# tinyusbboard.net
KiCad netlist of a schematic drawn in EAGLE
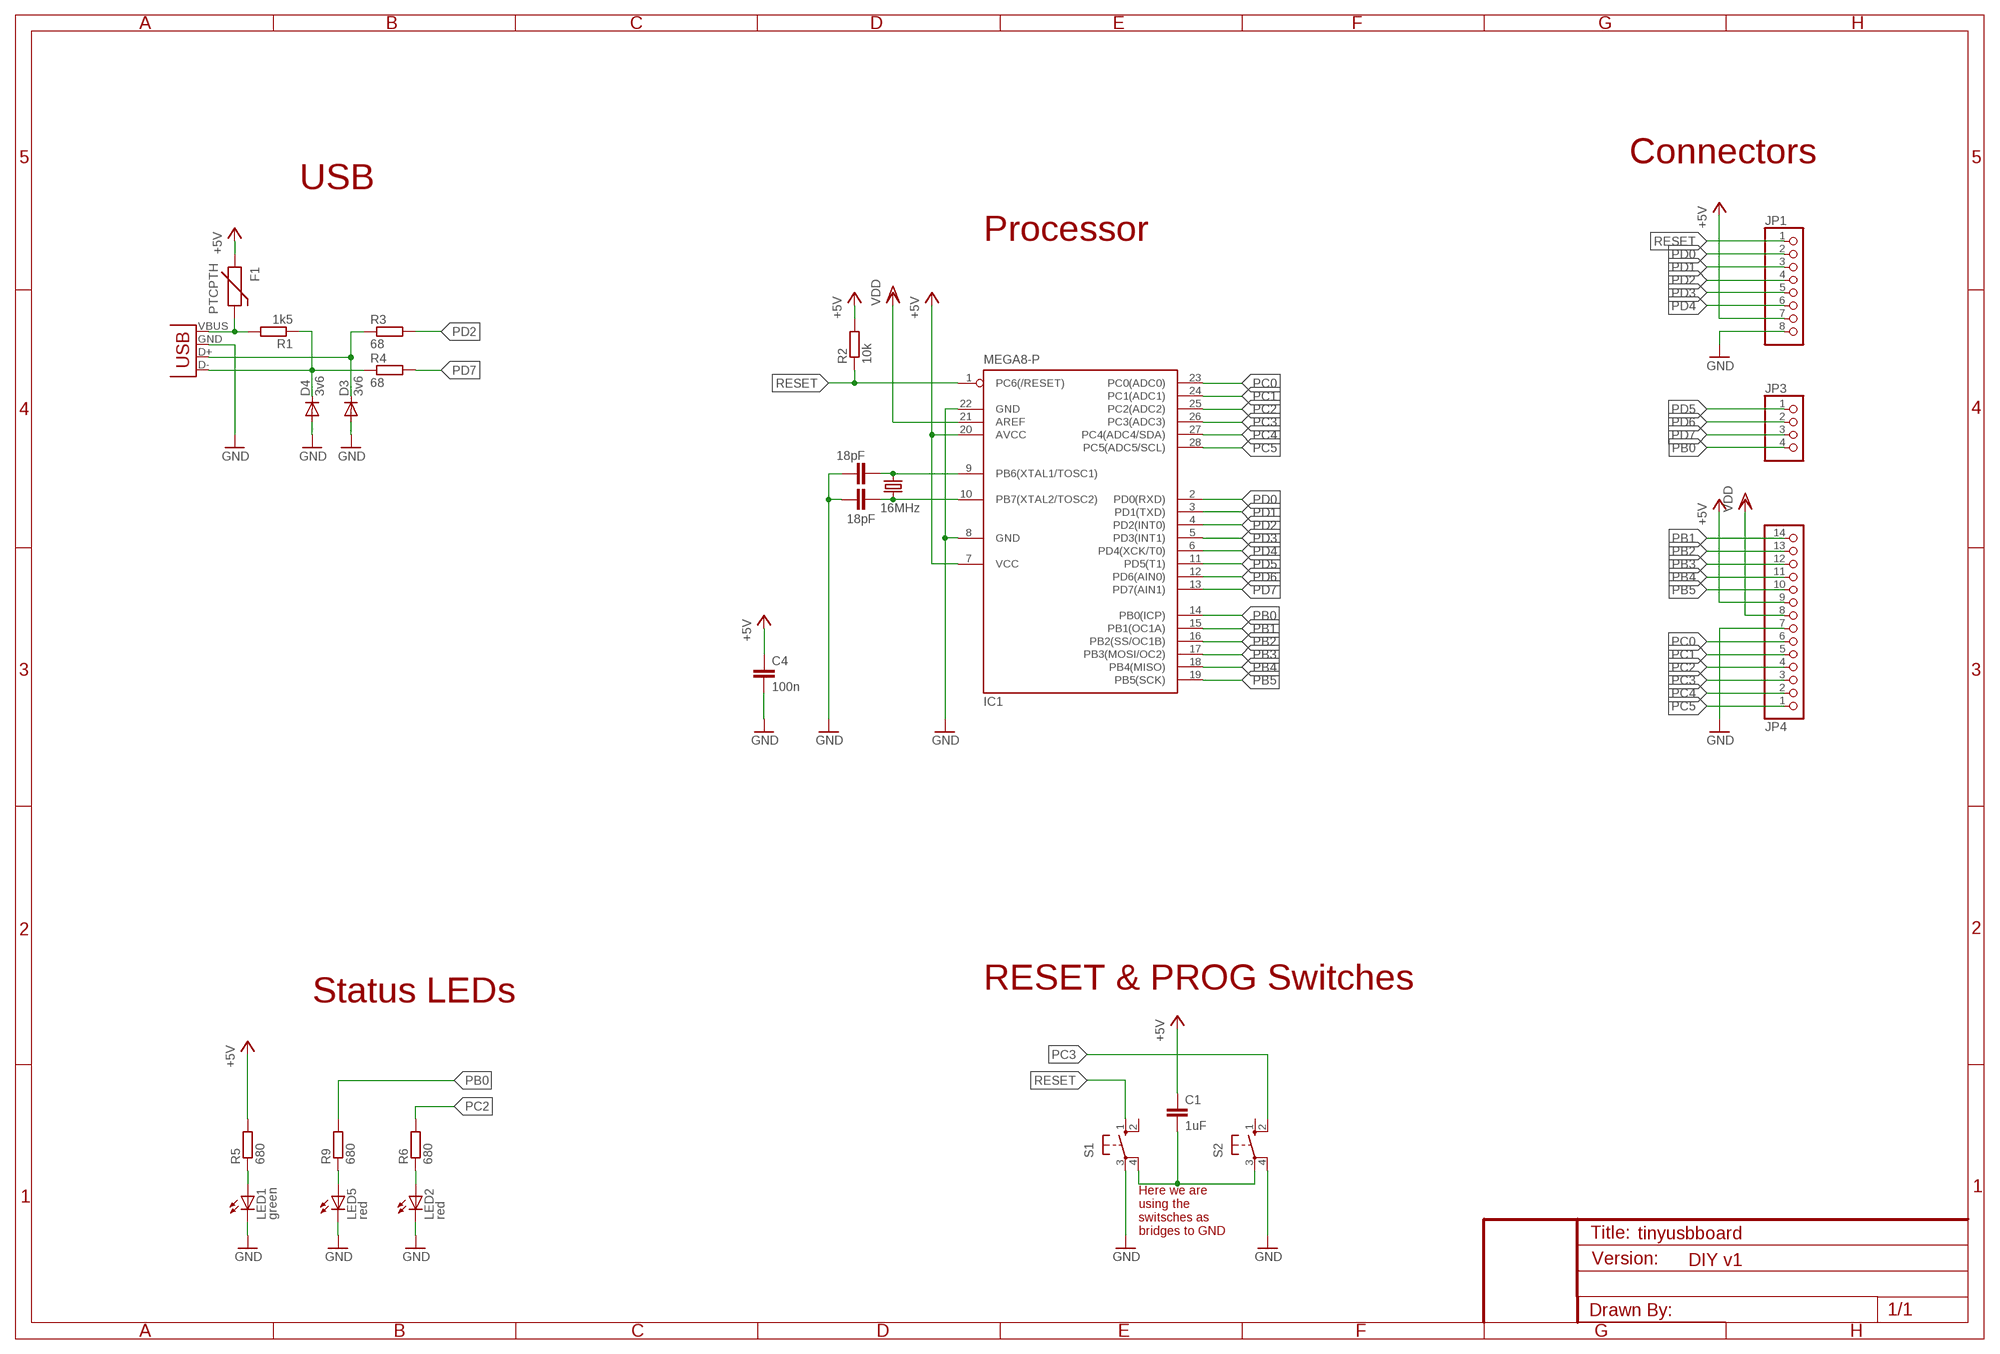
[diagram p0: schematic, sheet 1]

(export (version "E")
  (design (tool "Eeschema 10.0.6"))
  (components
    (comp (ref "C1")
      (value "1uF")
      (footprint "eagle-import:C0805")
      (libsource (lib "eagle-import") (part "C-EUC0805"))
    )
    (comp (ref "C2")
      (value "18pF")
      (footprint "eagle-import:C0805K")
      (libsource (lib "eagle-import") (part "resistor_C-EUC0805K"))
    )
    (comp (ref "C3")
      (value "18pF")
      (footprint "eagle-import:C0805K")
      (libsource (lib "eagle-import") (part "resistor_C-EUC0805K"))
    )
    (comp (ref "C4")
      (value "100n")
      (footprint "eagle-import:C0805")
      (libsource (lib "eagle-import") (part "C-EUC0805"))
    )
    (comp (ref "D3")
      (value "3v6")
      (footprint "eagle-import:MINIMELF")
      (libsource (lib "eagle-import") (part "DIODE-MINIMELF"))
    )
    (comp (ref "D4")
      (value "3v6")
      (footprint "eagle-import:MINIMELF")
      (libsource (lib "eagle-import") (part "DIODE-MINIMELF"))
    )
    (comp (ref "F1")
      (value "PTCPTH")
      (footprint "eagle-import:PTC")
      (libsource (lib "eagle-import") (part "PTCPTH"))
    )
    (comp (ref "IC1")
      (value "MEGA8-P")
      (footprint "eagle-import:DIL28-3")
      (libsource (lib "eagle-import") (part "MEGA8-P"))
    )
    (comp (ref "JP1")
      (value "PINHD-1X8")
      (footprint "eagle-import:1X08")
      (libsource (lib "eagle-import") (part "PINHD-1X8"))
    )
    (comp (ref "JP3")
      (value "PINHD-1X4")
      (footprint "eagle-import:1X04")
      (libsource (lib "eagle-import") (part "PINHD-1X4"))
    )
    (comp (ref "JP4")
      (value "PINHD-1X14")
      (footprint "eagle-import:1X14")
      (libsource (lib "eagle-import") (part "PINHD-1X14"))
    )
    (comp (ref "JP5")
      (value "USB-A-H")
      (footprint "eagle-import:USB-A-H")
      (libsource (lib "eagle-import") (part "USB-A-H"))
    )
    (comp (ref "LED1")
      (value "green")
      (footprint "eagle-import:CHIPLED_0805")
      (libsource (lib "eagle-import") (part "LEDCHIPLED_0805"))
    )
    (comp (ref "LED2")
      (value "red")
      (footprint "eagle-import:CHIPLED_0805")
      (libsource (lib "eagle-import") (part "LEDCHIPLED_0805"))
    )
    (comp (ref "LED5")
      (value "red")
      (footprint "eagle-import:CHIPLED_0805")
      (libsource (lib "eagle-import") (part "LEDCHIPLED_0805"))
    )
    (comp (ref "Q1")
      (value "16MHz")
      (footprint "eagle-import:HC49_S")
      (libsource (lib "eagle-import") (part "CRYSTALHC49S"))
    )
    (comp (ref "R1")
      (value "1k5")
      (footprint "eagle-import:M0805")
      (libsource (lib "eagle-import") (part "R-EU_M0805"))
    )
    (comp (ref "R2")
      (value "10k")
      (footprint "eagle-import:R1206")
      (libsource (lib "eagle-import") (part "R-EU_R1206"))
    )
    (comp (ref "R3")
      (value "68")
      (footprint "eagle-import:M0805")
      (libsource (lib "eagle-import") (part "R-EU_M0805"))
    )
    (comp (ref "R4")
      (value "68")
      (footprint "eagle-import:M0805")
      (libsource (lib "eagle-import") (part "R-EU_M0805"))
    )
    (comp (ref "R5")
      (value "680")
      (footprint "eagle-import:R0805")
      (libsource (lib "eagle-import") (part "R-EU_R0805"))
    )
    (comp (ref "R6")
      (value "680")
      (footprint "eagle-import:R0805")
      (libsource (lib "eagle-import") (part "R-EU_R0805"))
    )
    (comp (ref "R9")
      (value "680")
      (footprint "eagle-import:R0805")
      (libsource (lib "eagle-import") (part "R-EU_R0805"))
    )
    (comp (ref "S1")
      (value "10-XX")
      (footprint "eagle-import:B3F-10XX")
      (fields (field (name "MPN") "B3F-1000"))
      (libsource (lib "eagle-import") (part "10-XX"))
    )
    (comp (ref "S2")
      (value "10-XX")
      (footprint "eagle-import:B3F-10XX")
      (fields (field (name "MPN") "B3F-1000"))
      (libsource (lib "eagle-import") (part "10-XX"))
    )
  )
  (nets
    (net (code "1") (name "+5V") (class "Default")
      (node (ref "C1") (pin "1") (pinfunction "1_1") (pintype "passive"))
      (node (ref "C4") (pin "1") (pinfunction "1_1") (pintype "passive"))
      (node (ref "F1") (pin "P$1") (pinfunction "1_P$1") (pintype "bidirectional"))
      (node (ref "IC1") (pin "20") (pinfunction "AVCC_20") (pintype "power_in"))
      (node (ref "IC1") (pin "7") (pinfunction "VCC_7") (pintype "power_in"))
      (node (ref "JP1") (pin "7") (pinfunction "7_7") (pintype "passive"))
      (node (ref "JP4") (pin "9") (pinfunction "9_9") (pintype "passive"))
      (node (ref "R2") (pin "2") (pinfunction "2_2") (pintype "passive"))
      (node (ref "R5") (pin "2") (pinfunction "2_2") (pintype "passive"))
    )
    (net (code "2") (name "GND") (class "Default")
      (node (ref "C2") (pin "2") (pinfunction "2_2") (pintype "passive"))
      (node (ref "C3") (pin "2") (pinfunction "2_2") (pintype "passive"))
      (node (ref "C4") (pin "2") (pinfunction "2_2") (pintype "passive"))
      (node (ref "D3") (pin "A") (pinfunction "A_A") (pintype "passive"))
      (node (ref "D4") (pin "A") (pinfunction "A_A") (pintype "passive"))
      (node (ref "IC1") (pin "22") (pinfunction "GND_22") (pintype "power_in"))
      (node (ref "IC1") (pin "8") (pinfunction "GND_8") (pintype "power_in"))
      (node (ref "JP1") (pin "8") (pinfunction "8_8") (pintype "passive"))
      (node (ref "JP4") (pin "7") (pinfunction "7_7") (pintype "passive"))
      (node (ref "JP5") (pin "GND") (pinfunction "VBUS_GND") (pintype "bidirectional"))
      (node (ref "LED1") (pin "C") (pinfunction "C_C") (pintype "passive"))
      (node (ref "LED2") (pin "C") (pinfunction "C_C") (pintype "passive"))
      (node (ref "LED5") (pin "C") (pinfunction "C_C") (pintype "passive"))
      (node (ref "S1") (pin "3") (pinfunction "P_3") (pintype "passive"))
      (node (ref "S2") (pin "4") (pinfunction "P1_4") (pintype "passive"))
    )
    (net (code "3") (name "Net-(F1-2)") (class "Default")
      (node (ref "F1") (pin "P$2") (pinfunction "2_P$2") (pintype "bidirectional"))
      (node (ref "JP5") (pin "VBUS") (pinfunction "GND_VBUS") (pintype "bidirectional"))
      (node (ref "R1") (pin "2") (pinfunction "2_2") (pintype "passive"))
    )
    (net (code "4") (name "Net-(IC1-PB6(XTAL1{slash}TOSC1))") (class "Default")
      (node (ref "C3") (pin "1") (pinfunction "1_1") (pintype "passive"))
      (node (ref "IC1") (pin "9") (pinfunction "PB6(XTAL1/TOSC1)_9") (pintype "bidirectional"))
      (node (ref "Q1") (pin "1") (pinfunction "1_1") (pintype "passive"))
    )
    (net (code "5") (name "Net-(IC1-PB7(XTAL2{slash}TOSC2))") (class "Default")
      (node (ref "C2") (pin "1") (pinfunction "1_1") (pintype "passive"))
      (node (ref "IC1") (pin "10") (pinfunction "PB7(XTAL2/TOSC2)_10") (pintype "bidirectional"))
      (node (ref "Q1") (pin "2") (pinfunction "2_2") (pintype "passive"))
    )
    (net (code "6") (name "Net-(JP5-D+)") (class "Default")
      (node (ref "D4") (pin "C") (pinfunction "C_C") (pintype "passive"))
      (node (ref "JP5") (pin "D-") (pinfunction "D+_D-") (pintype "bidirectional"))
      (node (ref "R1") (pin "1") (pinfunction "1_1") (pintype "passive"))
      (node (ref "R4") (pin "1") (pinfunction "1_1") (pintype "passive"))
    )
    (net (code "7") (name "Net-(JP5-D-)") (class "Default")
      (node (ref "D3") (pin "C") (pinfunction "C_C") (pintype "passive"))
      (node (ref "JP5") (pin "D+") (pinfunction "D-_D+") (pintype "bidirectional"))
      (node (ref "R3") (pin "1") (pinfunction "1_1") (pintype "passive"))
    )
    (net (code "8") (name "Net-(LED1-PadA)") (class "Default")
      (node (ref "LED1") (pin "A") (pinfunction "A_A") (pintype "passive"))
      (node (ref "R5") (pin "1") (pinfunction "1_1") (pintype "passive"))
    )
    (net (code "9") (name "Net-(LED2-PadA)") (class "Default")
      (node (ref "LED2") (pin "A") (pinfunction "A_A") (pintype "passive"))
      (node (ref "R6") (pin "1") (pinfunction "1_1") (pintype "passive"))
    )
    (net (code "10") (name "Net-(LED5-PadA)") (class "Default")
      (node (ref "LED5") (pin "A") (pinfunction "A_A") (pintype "passive"))
      (node (ref "R9") (pin "1") (pinfunction "1_1") (pintype "passive"))
    )
    (net (code "11") (name "Net-(S1-P1)") (class "Default")
      (node (ref "C1") (pin "2") (pinfunction "2_2") (pintype "passive"))
      (node (ref "S1") (pin "4") (pinfunction "P1_4") (pintype "passive"))
      (node (ref "S2") (pin "3") (pinfunction "P_3") (pintype "passive"))
    )
    (net (code "12") (name "PB0") (class "Default")
      (node (ref "IC1") (pin "14") (pinfunction "PB0(ICP)_14") (pintype "bidirectional"))
      (node (ref "JP3") (pin "4") (pinfunction "4_4") (pintype "passive"))
      (node (ref "R9") (pin "2") (pinfunction "2_2") (pintype "passive"))
    )
    (net (code "13") (name "PB1") (class "Default")
      (node (ref "IC1") (pin "15") (pinfunction "PB1(OC1A)_15") (pintype "bidirectional"))
      (node (ref "JP4") (pin "14") (pinfunction "14_14") (pintype "passive"))
    )
    (net (code "14") (name "PB2") (class "Default")
      (node (ref "IC1") (pin "16") (pinfunction "PB2(SS/OC1B)_16") (pintype "bidirectional"))
      (node (ref "JP4") (pin "13") (pinfunction "13_13") (pintype "passive"))
    )
    (net (code "15") (name "PB3") (class "Default")
      (node (ref "IC1") (pin "17") (pinfunction "PB3(MOSI/OC2)_17") (pintype "bidirectional"))
      (node (ref "JP4") (pin "12") (pinfunction "12_12") (pintype "passive"))
    )
    (net (code "16") (name "PB4") (class "Default")
      (node (ref "IC1") (pin "18") (pinfunction "PB4(MISO)_18") (pintype "bidirectional"))
      (node (ref "JP4") (pin "11") (pinfunction "11_11") (pintype "passive"))
    )
    (net (code "17") (name "PB5") (class "Default")
      (node (ref "IC1") (pin "19") (pinfunction "PB5(SCK)_19") (pintype "bidirectional"))
      (node (ref "JP4") (pin "10") (pinfunction "10_10") (pintype "passive"))
    )
    (net (code "18") (name "PC0") (class "Default")
      (node (ref "IC1") (pin "23") (pinfunction "PC0(ADC0)_23") (pintype "bidirectional"))
      (node (ref "JP4") (pin "6") (pinfunction "6_6") (pintype "passive"))
    )
    (net (code "19") (name "PC1") (class "Default")
      (node (ref "IC1") (pin "24") (pinfunction "PC1(ADC1)_24") (pintype "bidirectional"))
      (node (ref "JP4") (pin "5") (pinfunction "5_5") (pintype "passive"))
    )
    (net (code "20") (name "PC2") (class "Default")
      (node (ref "IC1") (pin "25") (pinfunction "PC2(ADC2)_25") (pintype "bidirectional"))
      (node (ref "JP4") (pin "4") (pinfunction "4_4") (pintype "passive"))
      (node (ref "R6") (pin "2") (pinfunction "2_2") (pintype "passive"))
    )
    (net (code "21") (name "PC3") (class "Default")
      (node (ref "IC1") (pin "26") (pinfunction "PC3(ADC3)_26") (pintype "bidirectional"))
      (node (ref "JP4") (pin "3") (pinfunction "3_3") (pintype "passive"))
      (node (ref "S2") (pin "2") (pinfunction "S1_2") (pintype "passive"))
    )
    (net (code "22") (name "PC4") (class "Default")
      (node (ref "IC1") (pin "27") (pinfunction "PC4(ADC4/SDA)_27") (pintype "bidirectional"))
      (node (ref "JP4") (pin "2") (pinfunction "2_2") (pintype "passive"))
    )
    (net (code "23") (name "PC5") (class "Default")
      (node (ref "IC1") (pin "28") (pinfunction "PC5(ADC5/SCL)_28") (pintype "bidirectional"))
      (node (ref "JP4") (pin "1") (pinfunction "1_1") (pintype "passive"))
    )
    (net (code "24") (name "PD0") (class "Default")
      (node (ref "IC1") (pin "2") (pinfunction "PD0(RXD)_2") (pintype "bidirectional"))
      (node (ref "JP1") (pin "2") (pinfunction "2_2") (pintype "passive"))
    )
    (net (code "25") (name "PD1") (class "Default")
      (node (ref "IC1") (pin "3") (pinfunction "PD1(TXD)_3") (pintype "bidirectional"))
      (node (ref "JP1") (pin "3") (pinfunction "3_3") (pintype "passive"))
    )
    (net (code "26") (name "PD2") (class "Default")
      (node (ref "IC1") (pin "4") (pinfunction "PD2(INT0)_4") (pintype "bidirectional"))
      (node (ref "JP1") (pin "4") (pinfunction "4_4") (pintype "passive"))
      (node (ref "R3") (pin "2") (pinfunction "2_2") (pintype "passive"))
    )
    (net (code "27") (name "PD3") (class "Default")
      (node (ref "IC1") (pin "5") (pinfunction "PD3(INT1)_5") (pintype "bidirectional"))
      (node (ref "JP1") (pin "5") (pinfunction "5_5") (pintype "passive"))
    )
    (net (code "28") (name "PD4") (class "Default")
      (node (ref "IC1") (pin "6") (pinfunction "PD4(XCK/T0)_6") (pintype "bidirectional"))
      (node (ref "JP1") (pin "6") (pinfunction "6_6") (pintype "passive"))
    )
    (net (code "29") (name "PD5") (class "Default")
      (node (ref "IC1") (pin "11") (pinfunction "PD5(T1)_11") (pintype "bidirectional"))
      (node (ref "JP3") (pin "1") (pinfunction "1_1") (pintype "passive"))
    )
    (net (code "30") (name "PD6") (class "Default")
      (node (ref "IC1") (pin "12") (pinfunction "PD6(AIN0)_12") (pintype "bidirectional"))
      (node (ref "JP3") (pin "2") (pinfunction "2_2") (pintype "passive"))
    )
    (net (code "31") (name "PD7") (class "Default")
      (node (ref "IC1") (pin "13") (pinfunction "PD7(AIN1)_13") (pintype "bidirectional"))
      (node (ref "JP3") (pin "3") (pinfunction "3_3") (pintype "passive"))
      (node (ref "R4") (pin "2") (pinfunction "2_2") (pintype "passive"))
    )
    (net (code "32") (name "RESET") (class "Default")
      (node (ref "IC1") (pin "1") (pinfunction "PC6(/RESET)_1") (pintype "bidirectional"))
      (node (ref "JP1") (pin "1") (pinfunction "1_1") (pintype "passive"))
      (node (ref "R2") (pin "1") (pinfunction "1_1") (pintype "passive"))
      (node (ref "S1") (pin "1") (pinfunction "S_1") (pintype "passive"))
    )
    (net (code "33") (name "VDD") (class "Default")
      (node (ref "IC1") (pin "21") (pinfunction "AREF_21") (pintype "passive"))
      (node (ref "JP4") (pin "8") (pinfunction "8_8") (pintype "passive"))
    )
    (net (code "34") (name "unconnected-(S1-S1-Pad2)") (class "Default")
      (node (ref "S1") (pin "2") (pinfunction "S1_2") (pintype "passive"))
    )
    (net (code "35") (name "unconnected-(S2-S-Pad1)") (class "Default")
      (node (ref "S2") (pin "1") (pinfunction "S_1") (pintype "passive"))
    )
  )
)
